# TimerControl-NewAccel.net
KiCad netlist of a schematic drawn in EAGLE
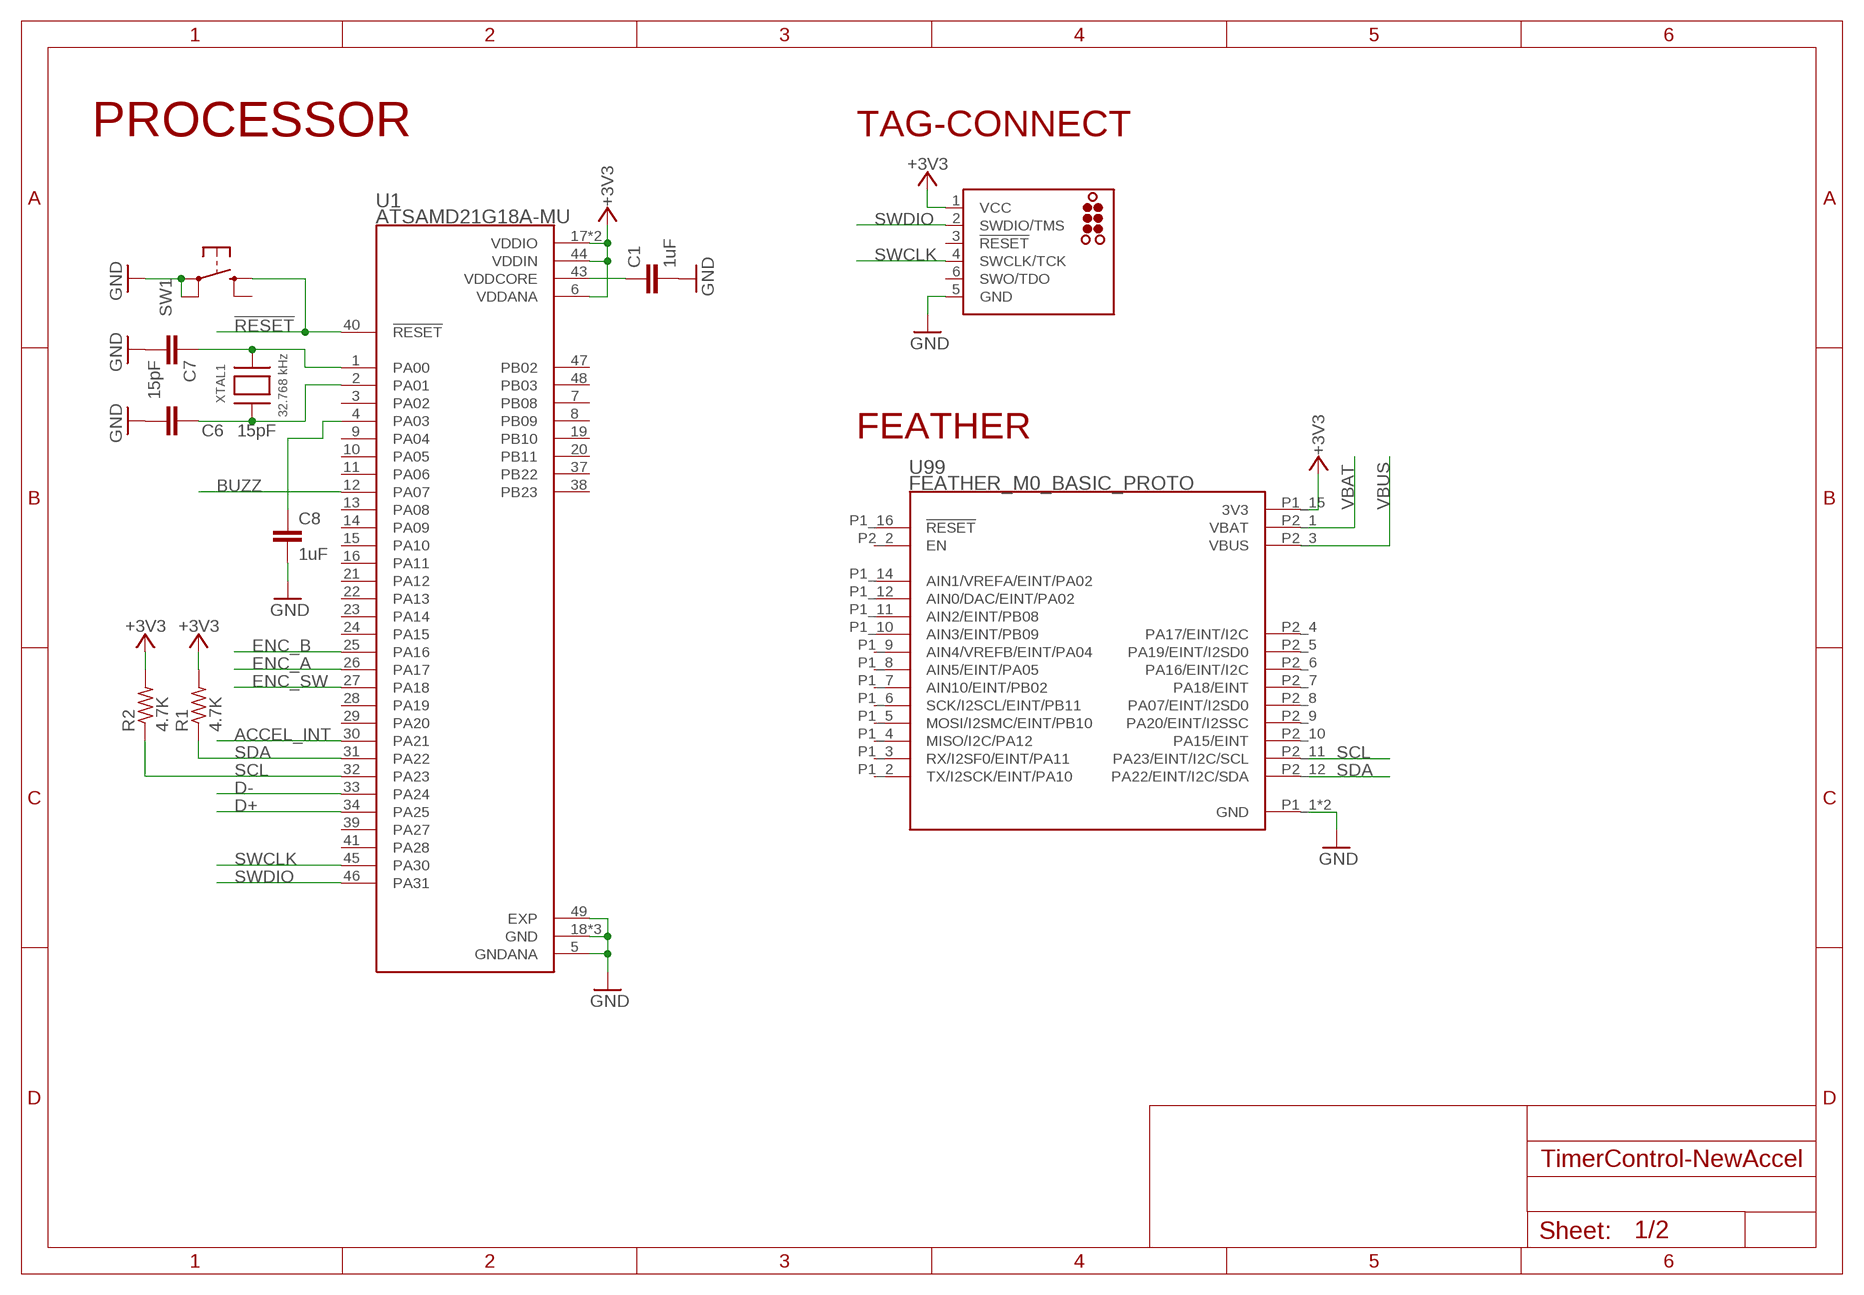
[diagram p0: schematic, sheet 1]
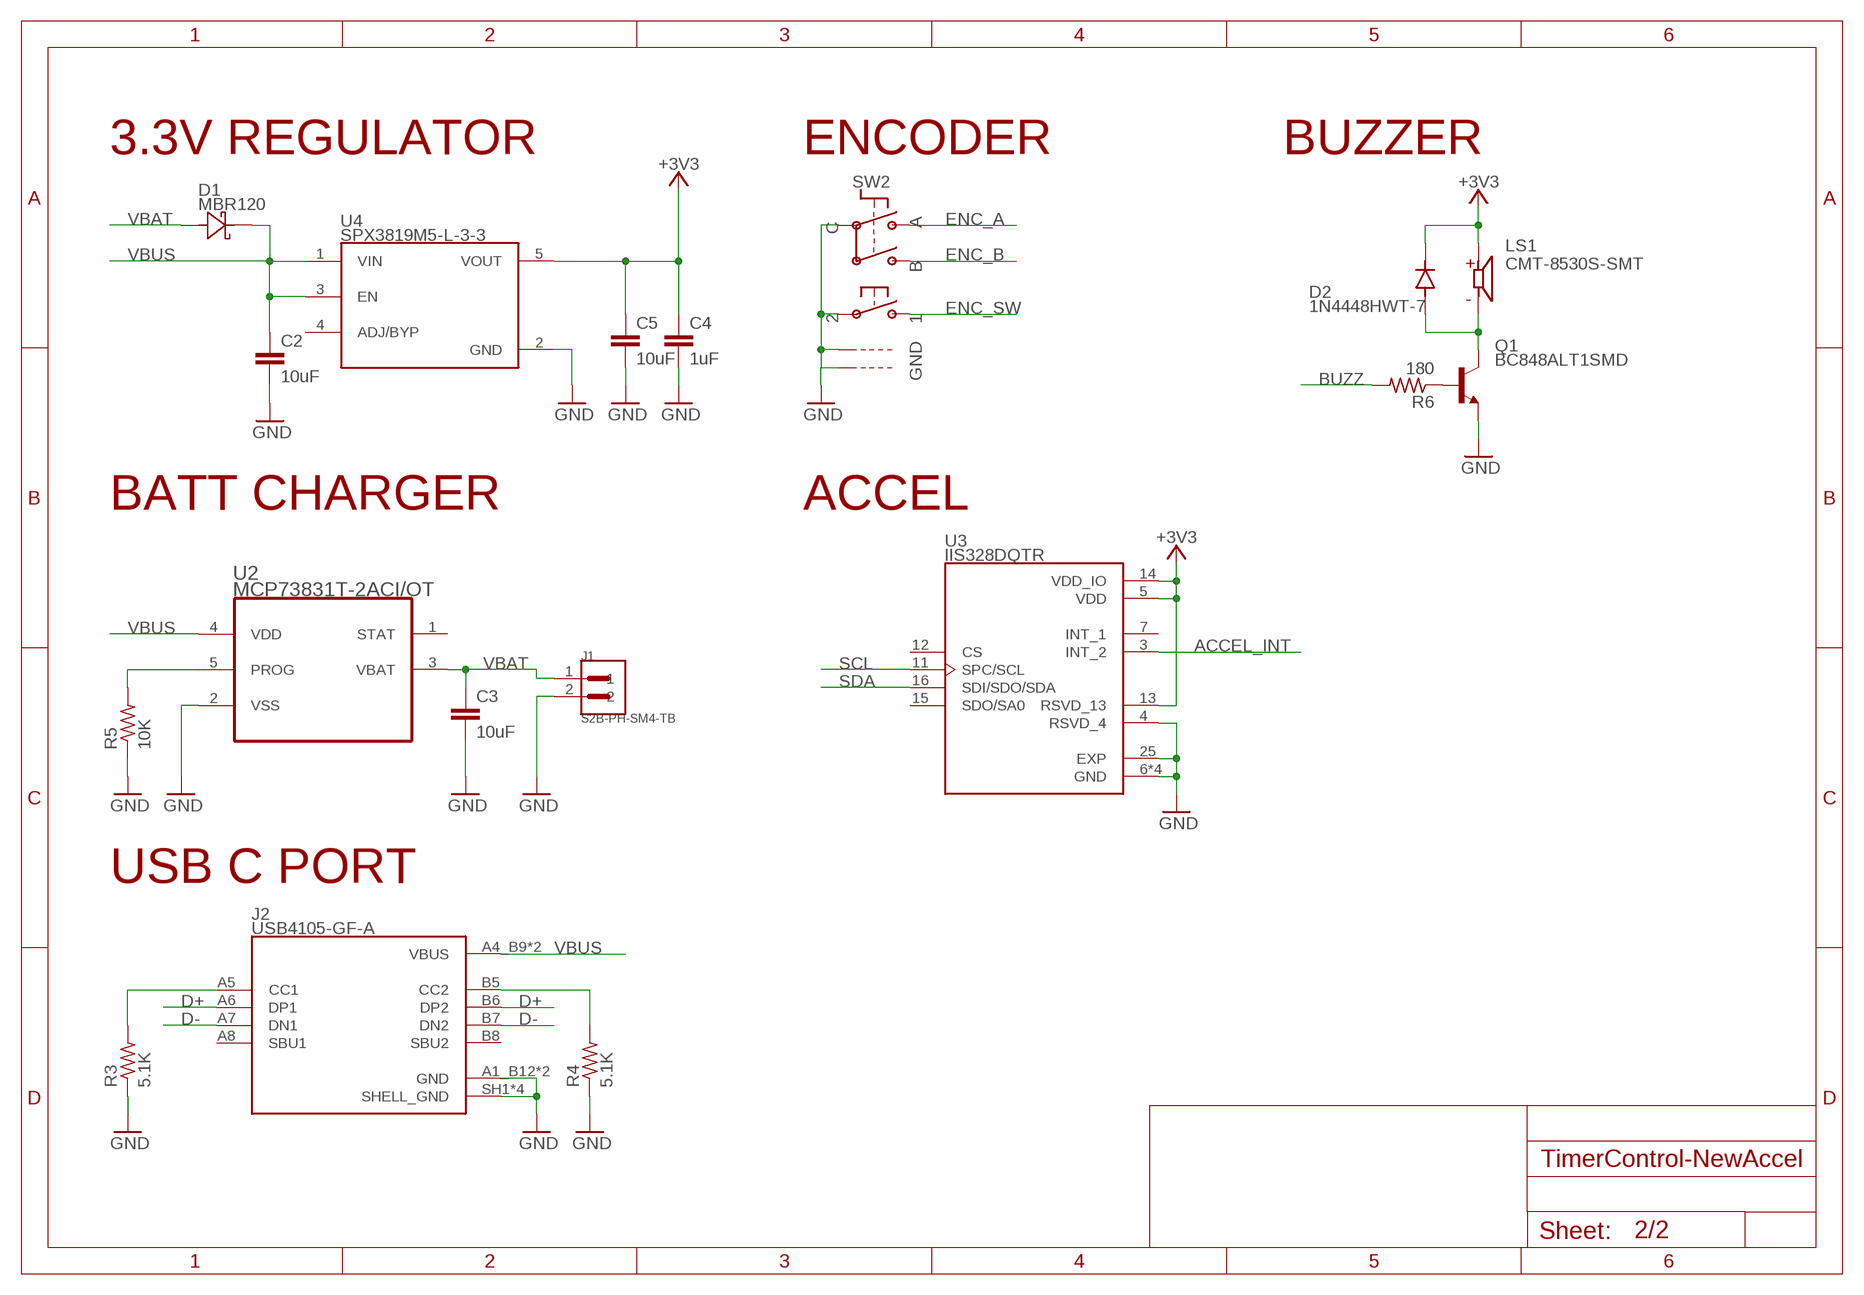
[diagram p1: schematic, sheet 2]

(export (version "E")
  (design (tool "Eeschema 10.0.6"))
  (components
    (comp (ref "C1")
      (value "1uF")
      (footprint "eagle-import:C0603")
      (libsource (lib "eagle-import") (part "C-EUC0603"))
    )
    (comp (ref "C6")
      (value "15pF")
      (footprint "eagle-import:C0603")
      (libsource (lib "eagle-import") (part "C-EUC0603"))
    )
    (comp (ref "C7")
      (value "15pF")
      (footprint "eagle-import:C0603")
      (libsource (lib "eagle-import") (part "C-EUC0603"))
    )
    (comp (ref "C8")
      (value "1uF")
      (footprint "eagle-import:C0603")
      (libsource (lib "eagle-import") (part "C-EUC0603"))
    )
    (comp (ref "J3")
      (value "TC2030_SWD-MCP-NL")
      (footprint "eagle-import:TC2030-MCP-NL")
      (libsource (lib "eagle-import") (part "TC2030_SWD-MCP-NL"))
    )
    (comp (ref "R1")
      (value "4.7K")
      (footprint "eagle-import:R0603")
      (libsource (lib "eagle-import") (part "R-US_R0603"))
    )
    (comp (ref "R2")
      (value "4.7K")
      (footprint "eagle-import:R0603")
      (libsource (lib "eagle-import") (part "R-US_R0603"))
    )
    (comp (ref "SW1")
      (value "KMR2")
      (footprint "eagle-import:2.80X4.60")
      (libsource (lib "eagle-import") (part "4PIN_SMD_BUTTON"))
    )
    (comp (ref "U1")
      (value "ATSAMD21G18A-MU")
      (footprint "eagle-import:QFN50P700X700X90-49N")
      (fields (field (name "MF") "Microchip"))
      (libsource (lib "eagle-import") (part "ATSAMD21G18A-MU"))
    )
    (comp (ref "U99")
      (value "FEATHER_M0_BASIC_PROTO")
      (footprint "eagle-import:MODULE_FEATHER_M0_BASIC_PROTO")
      (fields (field (name "MF") "Adafruit Industries") (field (name "MP") "Feather M0 Basic Proto"))
      (libsource (lib "eagle-import") (part "FEATHER_M0_BASIC_PROTO"))
    )
    (comp (ref "XTAL1")
      (value "32.768 kHz")
      (footprint "eagle-import:XTAL3215")
      (libsource (lib "eagle-import") (part "XTAL"))
    )
    (comp (ref "C2")
      (value "10uF")
      (footprint "eagle-import:C0603")
      (libsource (lib "eagle-import") (part "C-EUC0603"))
    )
    (comp (ref "C3")
      (value "10uF")
      (footprint "eagle-import:C0603")
      (libsource (lib "eagle-import") (part "C-EUC0603"))
    )
    (comp (ref "C4")
      (value "1uF")
      (footprint "eagle-import:C0603")
      (libsource (lib "eagle-import") (part "C-EUC0603"))
    )
    (comp (ref "C5")
      (value "10uF")
      (footprint "eagle-import:C0603")
      (fields (field (name "REV") "B"))
      (libsource (lib "eagle-import") (part "C-EUC0603"))
    )
    (comp (ref "D1")
      (value "MBR120")
      (footprint "eagle-import:SOD−123FL")
      (libsource (lib "eagle-import") (part "MBR120"))
    )
    (comp (ref "D2")
      (value "1N4448HWT-7")
      (footprint "eagle-import:SODFL1608X65N")
      (fields (field (name "MF") "Diodes Inc."))
      (libsource (lib "eagle-import") (part "1N4448HWT-7"))
    )
    (comp (ref "J1")
      (value "S2B-PH-SM4-TB")
      (footprint "eagle-import:JST_S2B-PH-SM4-TB")
      (fields (field (name "MANUFACTURER") "JST"))
      (libsource (lib "eagle-import") (part "S2B-PH-SM4-TB"))
    )
    (comp (ref "J2")
      (value "USB4105-GF-A")
      (footprint "eagle-import:GCT_USB4105-GF-A")
      (fields (field (name "MANUFACTURER") "Global Connector Technology"))
      (libsource (lib "eagle-import") (part "USB4105-GF-A"))
    )
    (comp (ref "LS1")
      (value "CMT-8530S-SMT")
      (footprint "eagle-import:CUI_CMT-8530S-SMT")
      (fields (field (name "MF") "CUI"))
      (libsource (lib "eagle-import") (part "CMT-8530S-SMT"))
    )
    (comp (ref "Q1")
      (value "BC848ALT1SMD")
      (footprint "eagle-import:SOT23")
      (libsource (lib "eagle-import") (part "BC848SMDALT1"))
    )
    (comp (ref "R3")
      (value "5.1K")
      (footprint "eagle-import:R0603")
      (libsource (lib "eagle-import") (part "R-US_R0603"))
    )
    (comp (ref "R4")
      (value "5.1K")
      (footprint "eagle-import:R0603")
      (libsource (lib "eagle-import") (part "R-US_R0603"))
    )
    (comp (ref "R5")
      (value "10K")
      (footprint "eagle-import:R0603")
      (libsource (lib "eagle-import") (part "R-US_R0603"))
    )
    (comp (ref "R6")
      (value "180")
      (footprint "eagle-import:R0603")
      (libsource (lib "eagle-import") (part "R-US_R0603"))
    )
    (comp (ref "SW2")
      (value "PEC11R_BOURNS_PEC11")
      (footprint "eagle-import:PEC11R")
      (libsource (lib "eagle-import") (part "PEC11R_PEC11_BOURNS"))
    )
    (comp (ref "U2")
      (value "MCP73831T-2ACI/OT")
      (footprint "eagle-import:SOT95P280X145-5N")
      (fields (field (name "DIGIKEY_PART_NUMBER") "MCP73831T-2ACI/OTTR-ND") (field (name "MF") "Microchip"))
      (libsource (lib "eagle-import") (part "MCP73831T-2ACI/OT"))
    )
    (comp (ref "U3")
      (value "IIS328DQTR")
      (footprint "eagle-import:QFN50P400X400X185-25N")
      (fields (field (name "MANUFACTURER") "ST Microelectronics"))
      (libsource (lib "eagle-import") (part "IIS328DQTR"))
    )
    (comp (ref "U4")
      (value "SPX3819M5-L-3-3")
      (footprint "eagle-import:SOT95P280X145-5N")
      (fields (field (name "MF") "MaxLinear"))
      (libsource (lib "eagle-import") (part "SPX3819M5-L-3-3"))
    )
  )
  (nets
    (net (code "1") (name "+3V3") (class "Default")
      (node (ref "C4") (pin "1") (pinfunction "1_1") (pintype "passive"))
      (node (ref "C5") (pin "1") (pinfunction "1_1") (pintype "passive"))
      (node (ref "D2") (pin "C") (pinfunction "K_C") (pintype "passive"))
      (node (ref "J3") (pin "1") (pinfunction "VCC_1") (pintype "passive"))
      (node (ref "LS1") (pin "P") (pinfunction "P_P") (pintype "passive"))
      (node (ref "R1") (pin "2") (pinfunction "2_2") (pintype "passive"))
      (node (ref "R2") (pin "2") (pinfunction "2_2") (pintype "passive"))
      (node (ref "U1") (pin "17") (pinfunction "VDDIO_17") (pintype "power_in"))
      (node (ref "U1") (pin "36") (pinfunction "VDDIO_36") (pintype "power_in"))
      (node (ref "U1") (pin "44") (pinfunction "VDDIN_44") (pintype "power_in"))
      (node (ref "U1") (pin "6") (pinfunction "VDDANA_6") (pintype "power_in"))
      (node (ref "U3") (pin "13") (pinfunction "RSVD_13_13") (pintype "passive"))
      (node (ref "U3") (pin "14") (pinfunction "VDD_IO_14") (pintype "power_in"))
      (node (ref "U3") (pin "5") (pinfunction "VDD_5") (pintype "power_in"))
      (node (ref "U4") (pin "5") (pinfunction "VOUT_5") (pintype "output"))
      (node (ref "U99") (pin "P1_15") (pinfunction "3V3_P1_15") (pintype "power_in"))
    )
    (net (code "2") (name "ACCEL_INT") (class "Default")
      (node (ref "U1") (pin "30") (pinfunction "PA21_30") (pintype "bidirectional"))
      (node (ref "U3") (pin "3") (pinfunction "INT_2_3") (pintype "output"))
    )
    (net (code "3") (name "BUZZ") (class "Default")
      (node (ref "R6") (pin "2") (pinfunction "2_2") (pintype "passive"))
      (node (ref "U1") (pin "12") (pinfunction "PA07_12") (pintype "bidirectional"))
    )
    (net (code "4") (name "D+") (class "Default")
      (node (ref "J2") (pin "A6") (pinfunction "DP1_A6") (pintype "bidirectional"))
      (node (ref "J2") (pin "B6") (pinfunction "DP2_B6") (pintype "bidirectional"))
      (node (ref "U1") (pin "34") (pinfunction "PA25_34") (pintype "bidirectional"))
    )
    (net (code "5") (name "D-") (class "Default")
      (node (ref "J2") (pin "A7") (pinfunction "DN1_A7") (pintype "bidirectional"))
      (node (ref "J2") (pin "B7") (pinfunction "DN2_B7") (pintype "bidirectional"))
      (node (ref "U1") (pin "33") (pinfunction "PA24_33") (pintype "bidirectional"))
    )
    (net (code "6") (name "ENC_A") (class "Default")
      (node (ref "SW2") (pin "P$A") (pinfunction "P$A_P$A") (pintype "passive"))
      (node (ref "U1") (pin "26") (pinfunction "PA17_26") (pintype "bidirectional"))
    )
    (net (code "7") (name "ENC_B") (class "Default")
      (node (ref "SW2") (pin "P$B") (pinfunction "P$B_P$B") (pintype "passive"))
      (node (ref "U1") (pin "25") (pinfunction "PA16_25") (pintype "bidirectional"))
    )
    (net (code "8") (name "ENC_SW") (class "Default")
      (node (ref "SW2") (pin "P$1") (pinfunction "P$1_P$1") (pintype "passive"))
      (node (ref "U1") (pin "27") (pinfunction "PA18_27") (pintype "bidirectional"))
    )
    (net (code "9") (name "GND") (class "Default")
      (node (ref "C1") (pin "2") (pinfunction "2_2") (pintype "passive"))
      (node (ref "C2") (pin "2") (pinfunction "2_2") (pintype "passive"))
      (node (ref "C3") (pin "2") (pinfunction "2_2") (pintype "passive"))
      (node (ref "C4") (pin "2") (pinfunction "2_2") (pintype "passive"))
      (node (ref "C5") (pin "2") (pinfunction "2_2") (pintype "passive"))
      (node (ref "C6") (pin "2") (pinfunction "2_2") (pintype "passive"))
      (node (ref "C7") (pin "2") (pinfunction "2_2") (pintype "passive"))
      (node (ref "C8") (pin "2") (pinfunction "2_2") (pintype "passive"))
      (node (ref "J1") (pin "2") (pinfunction "2_2") (pintype "passive"))
      (node (ref "J2") (pin "A1_B12") (pinfunction "GND_A1_B12") (pintype "power_in"))
      (node (ref "J2") (pin "B1_A12") (pinfunction "GND_B1_A12") (pintype "power_in"))
      (node (ref "J2") (pin "SH1") (pinfunction "SHELL_GND_SH1") (pintype "power_in"))
      (node (ref "J2") (pin "SH2") (pinfunction "SHELL_GND_SH2") (pintype "power_in"))
      (node (ref "J2") (pin "SH3") (pinfunction "SHELL_GND_SH3") (pintype "power_in"))
      (node (ref "J2") (pin "SH4") (pinfunction "SHELL_GND_SH4") (pintype "power_in"))
      (node (ref "J3") (pin "5") (pinfunction "GND_5") (pintype "passive"))
      (node (ref "Q1") (pin "2") (pinfunction "E_2") (pintype "passive"))
      (node (ref "R3") (pin "1") (pinfunction "1_1") (pintype "passive"))
      (node (ref "R4") (pin "1") (pinfunction "1_1") (pintype "passive"))
      (node (ref "R5") (pin "1") (pinfunction "1_1") (pintype "passive"))
      (node (ref "SW1") (pin "A") (pinfunction "P_A") (pintype "passive"))
      (node (ref "SW1") (pin "A'") (pinfunction "P1_A'") (pintype "passive"))
      (node (ref "SW2") (pin "P$2") (pinfunction "P$2_P$2") (pintype "passive"))
      (node (ref "SW2") (pin "P$C") (pinfunction "P$C_P$C") (pintype "passive"))
      (node (ref "SW2") (pin "P$GND1") (pinfunction "P$GND1_P$GND1") (pintype "passive"))
      (node (ref "SW2") (pin "P$GND2") (pinfunction "P$GND2_P$GND2") (pintype "passive"))
      (node (ref "U1") (pin "18") (pinfunction "GND_18") (pintype "power_in"))
      (node (ref "U1") (pin "35") (pinfunction "GND_35") (pintype "power_in"))
      (node (ref "U1") (pin "42") (pinfunction "GND_42") (pintype "power_in"))
      (node (ref "U1") (pin "49") (pinfunction "EXP_49") (pintype "power_in"))
      (node (ref "U1") (pin "5") (pinfunction "GNDANA_5") (pintype "power_in"))
      (node (ref "U2") (pin "2") (pinfunction "VSS_2") (pintype "power_in"))
      (node (ref "U3") (pin "10") (pinfunction "GND_10") (pintype "power_in"))
      (node (ref "U3") (pin "25") (pinfunction "EXP_25") (pintype "passive"))
      (node (ref "U3") (pin "4") (pinfunction "RSVD_4_4") (pintype "passive"))
      (node (ref "U3") (pin "6") (pinfunction "GND_6") (pintype "power_in"))
      (node (ref "U3") (pin "8") (pinfunction "GND_8") (pintype "power_in"))
      (node (ref "U3") (pin "9") (pinfunction "GND_9") (pintype "power_in"))
      (node (ref "U4") (pin "2") (pinfunction "GND_2") (pintype "passive"))
      (node (ref "U99") (pin "P1_1") (pinfunction "GND_P1_1") (pintype "power_in"))
      (node (ref "U99") (pin "P1_13") (pinfunction "GND_P1_13") (pintype "power_in"))
    )
    (net (code "10") (name "Net-(J2-CC1)") (class "Default")
      (node (ref "J2") (pin "A5") (pinfunction "CC1_A5") (pintype "bidirectional"))
      (node (ref "R3") (pin "2") (pinfunction "2_2") (pintype "passive"))
    )
    (net (code "11") (name "Net-(J2-CC2)") (class "Default")
      (node (ref "J2") (pin "B5") (pinfunction "CC2_B5") (pintype "bidirectional"))
      (node (ref "R4") (pin "2") (pinfunction "2_2") (pintype "passive"))
    )
    (net (code "12") (name "Net-(Q1-B)") (class "Default")
      (node (ref "Q1") (pin "1") (pinfunction "B_1") (pintype "passive"))
      (node (ref "R6") (pin "1") (pinfunction "1_1") (pintype "passive"))
    )
    (net (code "13") (name "Net-(Q1-C)") (class "Default")
      (node (ref "D2") (pin "A") (pinfunction "A_A") (pintype "passive"))
      (node (ref "LS1") (pin "N") (pinfunction "N_N") (pintype "passive"))
      (node (ref "Q1") (pin "3") (pinfunction "C_3") (pintype "passive"))
    )
    (net (code "14") (name "Net-(U1-PA00)") (class "Default")
      (node (ref "C7") (pin "1") (pinfunction "1_1") (pintype "passive"))
      (node (ref "U1") (pin "1") (pinfunction "PA00_1") (pintype "bidirectional"))
      (node (ref "XTAL1") (pin "P$2") (pinfunction "P$2_P$2") (pintype "bidirectional"))
    )
    (net (code "15") (name "Net-(U1-PA01)") (class "Default")
      (node (ref "C6") (pin "1") (pinfunction "1_1") (pintype "passive"))
      (node (ref "U1") (pin "2") (pinfunction "PA01_2") (pintype "bidirectional"))
      (node (ref "XTAL1") (pin "P$1") (pinfunction "P$1_P$1") (pintype "bidirectional"))
    )
    (net (code "16") (name "Net-(U1-PA03)") (class "Default")
      (node (ref "C8") (pin "1") (pinfunction "1_1") (pintype "passive"))
      (node (ref "U1") (pin "4") (pinfunction "PA03_4") (pintype "bidirectional"))
    )
    (net (code "17") (name "Net-(U1-VDDCORE)") (class "Default")
      (node (ref "C1") (pin "1") (pinfunction "1_1") (pintype "passive"))
      (node (ref "U1") (pin "43") (pinfunction "VDDCORE_43") (pintype "power_in"))
    )
    (net (code "18") (name "Net-(U2-PROG)") (class "Default")
      (node (ref "R5") (pin "2") (pinfunction "2_2") (pintype "passive"))
      (node (ref "U2") (pin "5") (pinfunction "PROG_5") (pintype "input"))
    )
    (net (code "19") (name "SCL") (class "Default")
      (node (ref "R2") (pin "1") (pinfunction "1_1") (pintype "passive"))
      (node (ref "U1") (pin "32") (pinfunction "PA23_32") (pintype "bidirectional"))
      (node (ref "U3") (pin "11") (pinfunction "SPC/SCL_11") (pintype "input"))
      (node (ref "U99") (pin "P2_11") (pinfunction "PA23/EINT/I2C/SCL_P2_11") (pintype "bidirectional"))
    )
    (net (code "20") (name "SDA") (class "Default")
      (node (ref "R1") (pin "1") (pinfunction "1_1") (pintype "passive"))
      (node (ref "U1") (pin "31") (pinfunction "PA22_31") (pintype "bidirectional"))
      (node (ref "U3") (pin "16") (pinfunction "SDI/SDO/SDA_16") (pintype "bidirectional"))
      (node (ref "U99") (pin "P2_12") (pinfunction "PA22/EINT/I2C/SDA_P2_12") (pintype "bidirectional"))
    )
    (net (code "21") (name "SWCLK") (class "Default")
      (node (ref "J3") (pin "4") (pinfunction "SWCLK/TCK_4") (pintype "output"))
      (node (ref "U1") (pin "45") (pinfunction "PA30_45") (pintype "bidirectional"))
    )
    (net (code "22") (name "SWDIO") (class "Default")
      (node (ref "J3") (pin "2") (pinfunction "SWDIO/TMS_2") (pintype "bidirectional"))
      (node (ref "U1") (pin "46") (pinfunction "PA31_46") (pintype "bidirectional"))
    )
    (net (code "23") (name "VBAT") (class "Default")
      (node (ref "C3") (pin "1") (pinfunction "1_1") (pintype "passive"))
      (node (ref "D1") (pin "A") (pinfunction "2_A") (pintype "passive"))
      (node (ref "J1") (pin "1") (pinfunction "1_1") (pintype "passive"))
      (node (ref "U2") (pin "3") (pinfunction "VBAT_3") (pintype "output"))
      (node (ref "U99") (pin "P2_1") (pinfunction "VBAT_P2_1") (pintype "power_in"))
    )
    (net (code "24") (name "VBUS") (class "Default")
      (node (ref "C2") (pin "1") (pinfunction "1_1") (pintype "passive"))
      (node (ref "D1") (pin "C") (pinfunction "1_C") (pintype "passive"))
      (node (ref "J2") (pin "A4_B9") (pinfunction "VBUS_A4_B9") (pintype "power_in"))
      (node (ref "J2") (pin "B4_A9") (pinfunction "VBUS_B4_A9") (pintype "power_in"))
      (node (ref "U2") (pin "4") (pinfunction "VDD_4") (pintype "power_in"))
      (node (ref "U4") (pin "1") (pinfunction "VIN_1") (pintype "power_in"))
      (node (ref "U4") (pin "3") (pinfunction "EN_3") (pintype "input"))
      (node (ref "U99") (pin "P2_3") (pinfunction "VBUS_P2_3") (pintype "power_in"))
    )
    (net (code "25") (name "unconnected-(J2-SBU1-PadA8)") (class "Default")
      (node (ref "J2") (pin "A8") (pinfunction "SBU1_A8") (pintype "bidirectional"))
    )
    (net (code "26") (name "unconnected-(J2-SBU2-PadB8)") (class "Default")
      (node (ref "J2") (pin "B8") (pinfunction "SBU2_B8") (pintype "bidirectional"))
    )
    (net (code "27") (name "unconnected-(J3-SWO{slash}TDO-Pad6)") (class "Default")
      (node (ref "J3") (pin "6") (pinfunction "SWO/TDO_6") (pintype "bidirectional"))
    )
    (net (code "28") (name "unconnected-(J3-~{RESET}-Pad3)") (class "Default")
      (node (ref "J3") (pin "3") (pinfunction "~{RESET}_3") (pintype "output"))
    )
    (net (code "29") (name "unconnected-(SW1-S1-PadB')") (class "Default")
      (node (ref "SW1") (pin "B'") (pinfunction "S1_B'") (pintype "passive"))
    )
    (net (code "30") (name "unconnected-(U1-PA02-Pad3)") (class "Default")
      (node (ref "U1") (pin "3") (pinfunction "PA02_3") (pintype "bidirectional"))
    )
    (net (code "31") (name "unconnected-(U1-PA04-Pad9)") (class "Default")
      (node (ref "U1") (pin "9") (pinfunction "PA04_9") (pintype "bidirectional"))
    )
    (net (code "32") (name "unconnected-(U1-PA05-Pad10)") (class "Default")
      (node (ref "U1") (pin "10") (pinfunction "PA05_10") (pintype "bidirectional"))
    )
    (net (code "33") (name "unconnected-(U1-PA06-Pad11)") (class "Default")
      (node (ref "U1") (pin "11") (pinfunction "PA06_11") (pintype "bidirectional"))
    )
    (net (code "34") (name "unconnected-(U1-PA08-Pad13)") (class "Default")
      (node (ref "U1") (pin "13") (pinfunction "PA08_13") (pintype "bidirectional"))
    )
    (net (code "35") (name "unconnected-(U1-PA09-Pad14)") (class "Default")
      (node (ref "U1") (pin "14") (pinfunction "PA09_14") (pintype "bidirectional"))
    )
    (net (code "36") (name "unconnected-(U1-PA10-Pad15)") (class "Default")
      (node (ref "U1") (pin "15") (pinfunction "PA10_15") (pintype "bidirectional"))
    )
    (net (code "37") (name "unconnected-(U1-PA11-Pad16)") (class "Default")
      (node (ref "U1") (pin "16") (pinfunction "PA11_16") (pintype "bidirectional"))
    )
    (net (code "38") (name "unconnected-(U1-PA12-Pad21)") (class "Default")
      (node (ref "U1") (pin "21") (pinfunction "PA12_21") (pintype "bidirectional"))
    )
    (net (code "39") (name "unconnected-(U1-PA13-Pad22)") (class "Default")
      (node (ref "U1") (pin "22") (pinfunction "PA13_22") (pintype "bidirectional"))
    )
    (net (code "40") (name "unconnected-(U1-PA14-Pad23)") (class "Default")
      (node (ref "U1") (pin "23") (pinfunction "PA14_23") (pintype "bidirectional"))
    )
    (net (code "41") (name "unconnected-(U1-PA15-Pad24)") (class "Default")
      (node (ref "U1") (pin "24") (pinfunction "PA15_24") (pintype "bidirectional"))
    )
    (net (code "42") (name "unconnected-(U1-PA19-Pad28)") (class "Default")
      (node (ref "U1") (pin "28") (pinfunction "PA19_28") (pintype "bidirectional"))
    )
    (net (code "43") (name "unconnected-(U1-PA20-Pad29)") (class "Default")
      (node (ref "U1") (pin "29") (pinfunction "PA20_29") (pintype "bidirectional"))
    )
    (net (code "44") (name "unconnected-(U1-PA27-Pad39)") (class "Default")
      (node (ref "U1") (pin "39") (pinfunction "PA27_39") (pintype "bidirectional"))
    )
    (net (code "45") (name "unconnected-(U1-PA28-Pad41)") (class "Default")
      (node (ref "U1") (pin "41") (pinfunction "PA28_41") (pintype "bidirectional"))
    )
    (net (code "46") (name "unconnected-(U1-PB02-Pad47)") (class "Default")
      (node (ref "U1") (pin "47") (pinfunction "PB02_47") (pintype "bidirectional"))
    )
    (net (code "47") (name "unconnected-(U1-PB03-Pad48)") (class "Default")
      (node (ref "U1") (pin "48") (pinfunction "PB03_48") (pintype "bidirectional"))
    )
    (net (code "48") (name "unconnected-(U1-PB08-Pad7)") (class "Default")
      (node (ref "U1") (pin "7") (pinfunction "PB08_7") (pintype "bidirectional"))
    )
    (net (code "49") (name "unconnected-(U1-PB09-Pad8)") (class "Default")
      (node (ref "U1") (pin "8") (pinfunction "PB09_8") (pintype "bidirectional"))
    )
    (net (code "50") (name "unconnected-(U1-PB10-Pad19)") (class "Default")
      (node (ref "U1") (pin "19") (pinfunction "PB10_19") (pintype "bidirectional"))
    )
    (net (code "51") (name "unconnected-(U1-PB11-Pad20)") (class "Default")
      (node (ref "U1") (pin "20") (pinfunction "PB11_20") (pintype "bidirectional"))
    )
    (net (code "52") (name "unconnected-(U1-PB22-Pad37)") (class "Default")
      (node (ref "U1") (pin "37") (pinfunction "PB22_37") (pintype "bidirectional"))
    )
    (net (code "53") (name "unconnected-(U1-PB23-Pad38)") (class "Default")
      (node (ref "U1") (pin "38") (pinfunction "PB23_38") (pintype "bidirectional"))
    )
    (net (code "54") (name "unconnected-(U2-STAT-Pad1)") (class "Default")
      (node (ref "U2") (pin "1") (pinfunction "STAT_1") (pintype "output"))
    )
    (net (code "55") (name "unconnected-(U3-CS-Pad12)") (class "Default")
      (node (ref "U3") (pin "12") (pinfunction "CS_12") (pintype "input"))
    )
    (net (code "56") (name "unconnected-(U3-INT_1-Pad7)") (class "Default")
      (node (ref "U3") (pin "7") (pinfunction "INT_1_7") (pintype "output"))
    )
    (net (code "57") (name "unconnected-(U3-SDO{slash}SA0-Pad15)") (class "Default")
      (node (ref "U3") (pin "15") (pinfunction "SDO/SA0_15") (pintype "bidirectional"))
    )
    (net (code "58") (name "unconnected-(U4-ADJ{slash}BYP-Pad4)") (class "Default")
      (node (ref "U4") (pin "4") (pinfunction "ADJ/BYP_4") (pintype "passive"))
    )
    (net (code "59") (name "unconnected-(U99-AIN0{slash}DAC{slash}EINT{slash}PA02-PadP1_12)") (class "Default")
      (node (ref "U99") (pin "P1_12") (pinfunction "AIN0/DAC/EINT/PA02_P1_12") (pintype "bidirectional"))
    )
    (net (code "60") (name "unconnected-(U99-AIN1{slash}VREFA{slash}EINT{slash}PA02-PadP1_14)") (class "Default")
      (node (ref "U99") (pin "P1_14") (pinfunction "AIN1/VREFA/EINT/PA02_P1_14") (pintype "bidirectional"))
    )
    (net (code "61") (name "unconnected-(U99-AIN2{slash}EINT{slash}PB08-PadP1_11)") (class "Default")
      (node (ref "U99") (pin "P1_11") (pinfunction "AIN2/EINT/PB08_P1_11") (pintype "bidirectional"))
    )
    (net (code "62") (name "unconnected-(U99-AIN3{slash}EINT{slash}PB09-PadP1_10)") (class "Default")
      (node (ref "U99") (pin "P1_10") (pinfunction "AIN3/EINT/PB09_P1_10") (pintype "bidirectional"))
    )
    (net (code "63") (name "unconnected-(U99-AIN4{slash}VREFB{slash}EINT{slash}PA04-PadP1_9)") (class "Default")
      (node (ref "U99") (pin "P1_9") (pinfunction "AIN4/VREFB/EINT/PA04_P1_9") (pintype "bidirectional"))
    )
    (net (code "64") (name "unconnected-(U99-AIN5{slash}EINT{slash}PA05-PadP1_8)") (class "Default")
      (node (ref "U99") (pin "P1_8") (pinfunction "AIN5/EINT/PA05_P1_8") (pintype "bidirectional"))
    )
    (net (code "65") (name "unconnected-(U99-AIN10{slash}EINT{slash}PB02-PadP1_7)") (class "Default")
      (node (ref "U99") (pin "P1_7") (pinfunction "AIN10/EINT/PB02_P1_7") (pintype "bidirectional"))
    )
    (net (code "66") (name "unconnected-(U99-EN-PadP2_2)") (class "Default")
      (node (ref "U99") (pin "P2_2") (pinfunction "EN_P2_2") (pintype "input"))
    )
    (net (code "67") (name "unconnected-(U99-MISO{slash}I2C{slash}PA12-PadP1_4)") (class "Default")
      (node (ref "U99") (pin "P1_4") (pinfunction "MISO/I2C/PA12_P1_4") (pintype "bidirectional"))
    )
    (net (code "68") (name "unconnected-(U99-MOSI{slash}I2SMC{slash}EINT{slash}PB10-PadP1_5)") (class "Default")
      (node (ref "U99") (pin "P1_5") (pinfunction "MOSI/I2SMC/EINT/PB10_P1_5") (pintype "bidirectional"))
    )
    (net (code "69") (name "unconnected-(U99-PA07{slash}EINT{slash}I2SD0-PadP2_8)") (class "Default")
      (node (ref "U99") (pin "P2_8") (pinfunction "PA07/EINT/I2SD0_P2_8") (pintype "bidirectional"))
    )
    (net (code "70") (name "unconnected-(U99-PA15{slash}EINT-PadP2_10)") (class "Default")
      (node (ref "U99") (pin "P2_10") (pinfunction "PA15/EINT_P2_10") (pintype "bidirectional"))
    )
    (net (code "71") (name "unconnected-(U99-PA16{slash}EINT{slash}I2C-PadP2_6)") (class "Default")
      (node (ref "U99") (pin "P2_6") (pinfunction "PA16/EINT/I2C_P2_6") (pintype "bidirectional"))
    )
    (net (code "72") (name "unconnected-(U99-PA17{slash}EINT{slash}I2C-PadP2_4)") (class "Default")
      (node (ref "U99") (pin "P2_4") (pinfunction "PA17/EINT/I2C_P2_4") (pintype "bidirectional"))
    )
    (net (code "73") (name "unconnected-(U99-PA18{slash}EINT-PadP2_7)") (class "Default")
      (node (ref "U99") (pin "P2_7") (pinfunction "PA18/EINT_P2_7") (pintype "bidirectional"))
    )
    (net (code "74") (name "unconnected-(U99-PA19{slash}EINT{slash}I2SD0-PadP2_5)") (class "Default")
      (node (ref "U99") (pin "P2_5") (pinfunction "PA19/EINT/I2SD0_P2_5") (pintype "bidirectional"))
    )
    (net (code "75") (name "unconnected-(U99-PA20{slash}EINT{slash}I2SSC-PadP2_9)") (class "Default")
      (node (ref "U99") (pin "P2_9") (pinfunction "PA20/EINT/I2SSC_P2_9") (pintype "bidirectional"))
    )
    (net (code "76") (name "unconnected-(U99-RX{slash}I2SF0{slash}EINT{slash}PA11-PadP1_3)") (class "Default")
      (node (ref "U99") (pin "P1_3") (pinfunction "RX/I2SF0/EINT/PA11_P1_3") (pintype "bidirectional"))
    )
    (net (code "77") (name "unconnected-(U99-SCK{slash}I2SCL{slash}EINT{slash}PB11-PadP1_6)") (class "Default")
      (node (ref "U99") (pin "P1_6") (pinfunction "SCK/I2SCL/EINT/PB11_P1_6") (pintype "bidirectional"))
    )
    (net (code "78") (name "unconnected-(U99-TX{slash}I2SCK{slash}EINT{slash}PA10-PadP1_2)") (class "Default")
      (node (ref "U99") (pin "P1_2") (pinfunction "TX/I2SCK/EINT/PA10_P1_2") (pintype "bidirectional"))
    )
    (net (code "79") (name "unconnected-(U99-~{RESET}-PadP1_16)") (class "Default")
      (node (ref "U99") (pin "P1_16") (pinfunction "~{RESET}_P1_16") (pintype "input"))
    )
    (net (code "80") (name "~{RESET}") (class "Default")
      (node (ref "SW1") (pin "B") (pinfunction "S_B") (pintype "passive"))
      (node (ref "U1") (pin "40") (pinfunction "~{RESET}_40") (pintype "input"))
    )
  )
)
